# shield_1_axis.net
KiCad netlist of a schematic drawn in EAGLE
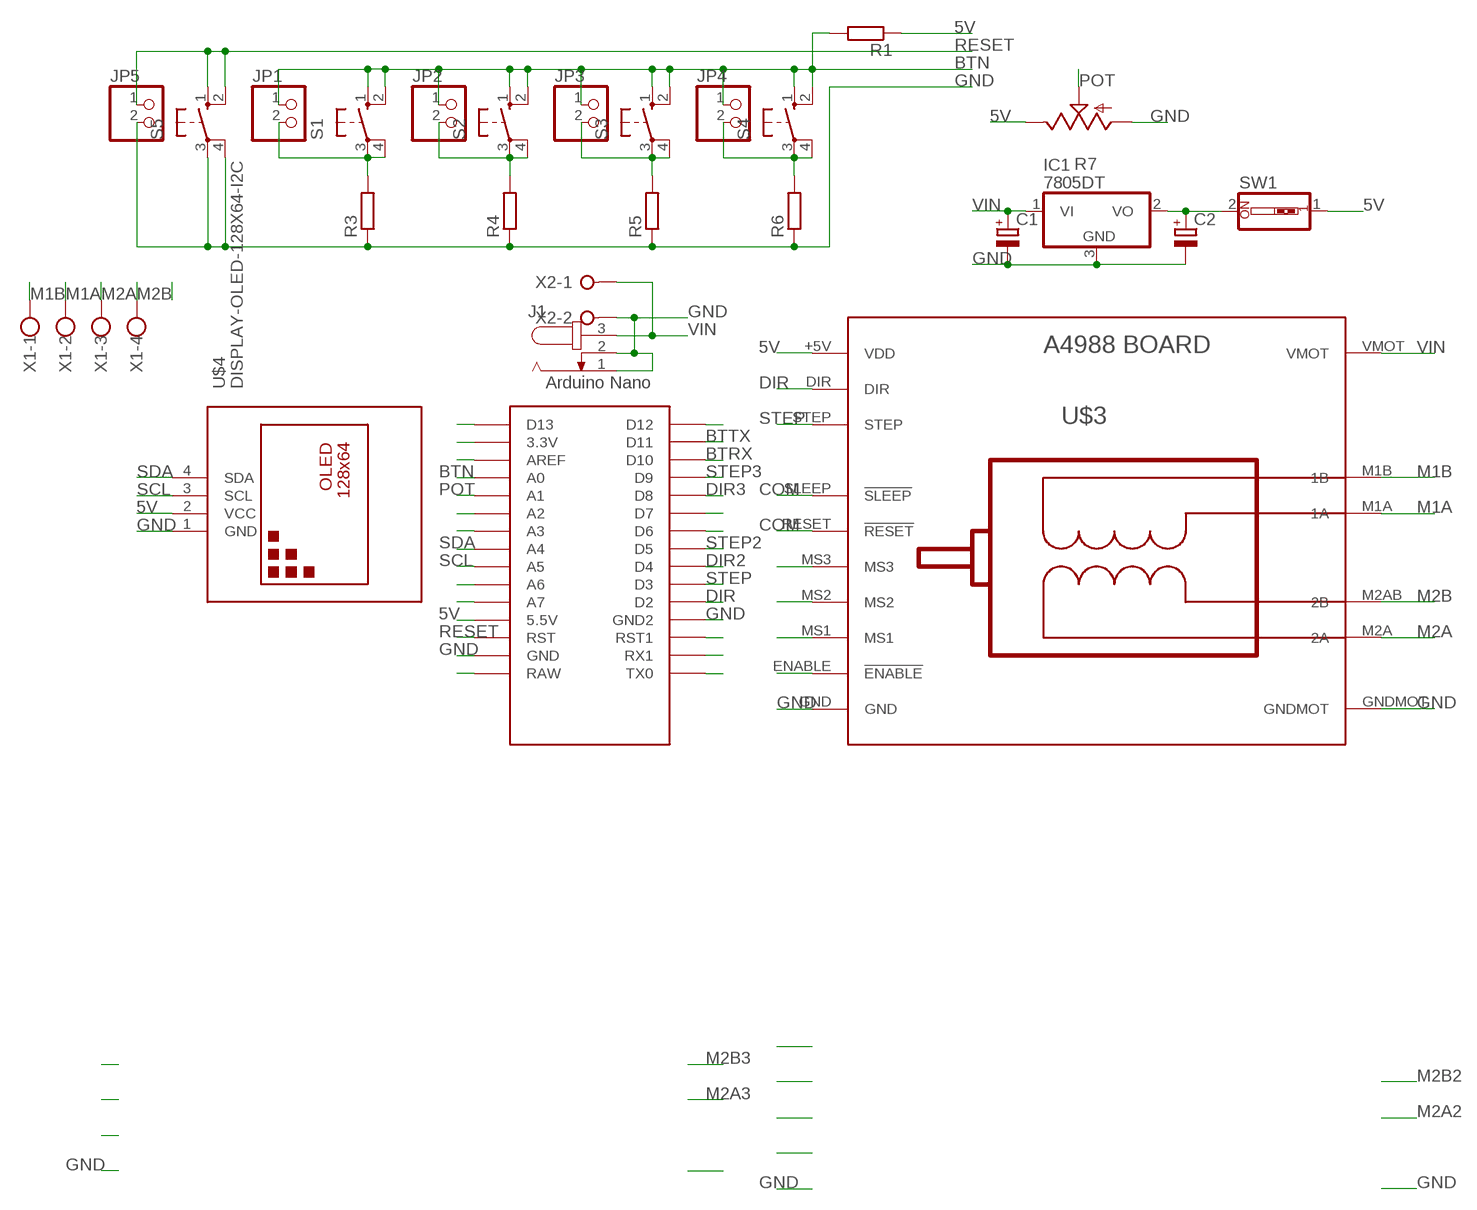
[diagram p0: schematic, sheet 1]

(export (version "E")
  (design (tool "Eeschema 10.0.6"))
  (components
    (comp (ref "C1")
      (value "CPOL-EUE2.5-7")
      (footprint "eagle-import:E2,5-7")
      (libsource (lib "eagle-import") (part "CPOL-EUE2.5-7"))
    )
    (comp (ref "C2")
      (value "CPOL-EUE2.5-7")
      (footprint "eagle-import:E2,5-7")
      (libsource (lib "eagle-import") (part "CPOL-EUE2.5-7"))
    )
    (comp (ref "IC1")
      (value "7805DT")
      (footprint "eagle-import:TO252")
      (libsource (lib "eagle-import") (part "78DT05"))
    )
    (comp (ref "J1")
      (value "JACK-PLUG1")
      (footprint "eagle-import:SPC4078")
      (libsource (lib "eagle-import") (part "JACK-PLUG1"))
    )
    (comp (ref "JP1")
      (value "PINHD-1X2")
      (footprint "eagle-import:1X02")
      (libsource (lib "eagle-import") (part "PINHD-1X2"))
    )
    (comp (ref "JP2")
      (value "PINHD-1X2")
      (footprint "eagle-import:1X02")
      (libsource (lib "eagle-import") (part "PINHD-1X2"))
    )
    (comp (ref "JP3")
      (value "PINHD-1X2")
      (footprint "eagle-import:1X02")
      (libsource (lib "eagle-import") (part "PINHD-1X2"))
    )
    (comp (ref "JP4")
      (value "PINHD-1X2")
      (footprint "eagle-import:1X02")
      (libsource (lib "eagle-import") (part "PINHD-1X2"))
    )
    (comp (ref "JP5")
      (value "PINHD-1X2")
      (footprint "eagle-import:1X02")
      (libsource (lib "eagle-import") (part "PINHD-1X2"))
    )
    (comp (ref "R1")
      (value "R-EU_R1206")
      (footprint "eagle-import:R1206")
      (libsource (lib "eagle-import") (part "R-EU_R1206"))
    )
    (comp (ref "R3")
      (value "R-EU_R1206")
      (footprint "eagle-import:R1206")
      (libsource (lib "eagle-import") (part "R-EU_R1206"))
    )
    (comp (ref "R4")
      (value "R-EU_R1206")
      (footprint "eagle-import:R1206")
      (libsource (lib "eagle-import") (part "R-EU_R1206"))
    )
    (comp (ref "R5")
      (value "R-EU_R1206")
      (footprint "eagle-import:R1206")
      (libsource (lib "eagle-import") (part "R-EU_R1206"))
    )
    (comp (ref "R6")
      (value "R-EU_R1206")
      (footprint "eagle-import:R1206")
      (libsource (lib "eagle-import") (part "R-EU_R1206"))
    )
    (comp (ref "R7")
      (value "TRIM_US-S63S")
      (footprint "eagle-import:S63S")
      (libsource (lib "eagle-import") (part "TRIM_US-S63S"))
    )
    (comp (ref "S1")
      (value "40-XX")
      (footprint "eagle-import:B3F-40XX")
      (fields (field (name "MF") "OMRON COMPONENTS USA") (field (name "MPN") "B3F-4000"))
      (libsource (lib "eagle-import") (part "40-XX"))
    )
    (comp (ref "S2")
      (value "40-XX")
      (footprint "eagle-import:B3F-40XX")
      (fields (field (name "MF") "OMRON COMPONENTS USA") (field (name "MPN") "B3F-4000"))
      (libsource (lib "eagle-import") (part "40-XX"))
    )
    (comp (ref "S3")
      (value "40-XX")
      (footprint "eagle-import:B3F-40XX")
      (fields (field (name "MF") "OMRON COMPONENTS USA") (field (name "MPN") "B3F-4000"))
      (libsource (lib "eagle-import") (part "40-XX"))
    )
    (comp (ref "S4")
      (value "40-XX")
      (footprint "eagle-import:B3F-40XX")
      (fields (field (name "MF") "OMRON COMPONENTS USA") (field (name "MPN") "B3F-4000"))
      (libsource (lib "eagle-import") (part "40-XX"))
    )
    (comp (ref "S5")
      (value "10-XX")
      (footprint "eagle-import:B3F-10XX")
      (fields (field (name "MPN") "B3F-1000"))
      (libsource (lib "eagle-import") (part "10-XX"))
    )
    (comp (ref "SW1")
      (value "SW_DIP-1")
      (footprint "eagle-import:EDG-01")
      (libsource (lib "eagle-import") (part "SW_DIP-1"))
    )
    (comp (ref "U$1")
      (value "NANO")
      (footprint "eagle-import:NANO")
      (libsource (lib "eagle-import") (part "NANO"))
    )
    (comp (ref "U$3")
      (value "BOARD_A4988")
      (footprint "eagle-import:BOARD_A4988")
      (libsource (lib "eagle-import") (part "BOARD_A4988"))
    )
    (comp (ref "U$4")
      (value "DISPLAY-OLED-128X64-I2C")
      (footprint "eagle-import:DISPLAY-OLED-128X64-I2C")
      (libsource (lib "eagle-import") (part "DISPLAY-OLED-128X64-I2C"))
    )
    (comp (ref "X1")
      (value "W237-4")
      (footprint "eagle-import:W237-4")
      (libsource (lib "eagle-import") (part "W237-4"))
    )
    (comp (ref "X2")
      (value "W237-02P")
      (footprint "eagle-import:W237-132")
      (libsource (lib "eagle-import") (part "W237-02P"))
    )
  )
  (nets
    (net (code "1") (name "/5V") (class "Default")
      (node (ref "R1") (pin "1") (pinfunction "1_1") (pintype "passive"))
      (node (ref "R7") (pin "E") (pinfunction "E_E") (pintype "passive"))
      (node (ref "SW1") (pin "1") (pinfunction "1_1") (pintype "passive"))
      (node (ref "U$1") (pin "5V") (pinfunction "5.5V_5V") (pintype "bidirectional"))
      (node (ref "U$3") (pin "+5V") (pinfunction "VDD_+5V") (pintype "power_in"))
      (node (ref "U$4") (pin "2") (pinfunction "VCC_2") (pintype "power_in"))
    )
    (net (code "2") (name "/BTN") (class "Default")
      (node (ref "JP1") (pin "1") (pinfunction "1_1") (pintype "passive"))
      (node (ref "JP2") (pin "1") (pinfunction "1_1") (pintype "passive"))
      (node (ref "JP3") (pin "1") (pinfunction "1_1") (pintype "passive"))
      (node (ref "JP4") (pin "1") (pinfunction "1_1") (pintype "passive"))
      (node (ref "R1") (pin "2") (pinfunction "2_2") (pintype "passive"))
      (node (ref "S1") (pin "1") (pinfunction "S_1") (pintype "passive"))
      (node (ref "S1") (pin "2") (pinfunction "S1_2") (pintype "passive"))
      (node (ref "S2") (pin "1") (pinfunction "S_1") (pintype "passive"))
      (node (ref "S2") (pin "2") (pinfunction "S1_2") (pintype "passive"))
      (node (ref "S3") (pin "1") (pinfunction "S_1") (pintype "passive"))
      (node (ref "S3") (pin "2") (pinfunction "S1_2") (pintype "passive"))
      (node (ref "S4") (pin "1") (pinfunction "S_1") (pintype "passive"))
      (node (ref "S4") (pin "2") (pinfunction "S1_2") (pintype "passive"))
      (node (ref "U$1") (pin "A0") (pinfunction "A0_A0") (pintype "bidirectional"))
    )
    (net (code "3") (name "/BTRX") (class "Default")
      (node (ref "U$1") (pin "D10") (pinfunction "D10_D10") (pintype "bidirectional"))
    )
    (net (code "4") (name "/BTTX") (class "Default")
      (node (ref "U$1") (pin "D11") (pinfunction "D11_D11") (pintype "bidirectional"))
    )
    (net (code "5") (name "/COM") (class "Default")
      (node (ref "U$3") (pin "RESET") (pinfunction "~{RESET}_RESET") (pintype "input"))
      (node (ref "U$3") (pin "SLEEP") (pinfunction "~{SLEEP}_SLEEP") (pintype "input"))
    )
    (net (code "6") (name "/DIR") (class "Default")
      (node (ref "U$1") (pin "D2") (pinfunction "D2_D2") (pintype "bidirectional"))
      (node (ref "U$3") (pin "DIR") (pinfunction "DIR_DIR") (pintype "input"))
    )
    (net (code "7") (name "/DIR2") (class "Default")
      (node (ref "U$1") (pin "D4") (pinfunction "D4_D4") (pintype "bidirectional"))
    )
    (net (code "8") (name "/DIR3") (class "Default")
      (node (ref "U$1") (pin "D8") (pinfunction "D8_D8") (pintype "bidirectional"))
    )
    (net (code "9") (name "/GND") (class "Default")
      (node (ref "C1") (pin "-") (pinfunction "-_-") (pintype "passive"))
      (node (ref "C2") (pin "-") (pinfunction "-_-") (pintype "passive"))
      (node (ref "IC1") (pin "3") (pinfunction "GND_3") (pintype "passive"))
      (node (ref "J1") (pin "1") (pinfunction "1_1") (pintype "passive"))
      (node (ref "J1") (pin "2") (pinfunction "2_2") (pintype "passive"))
      (node (ref "JP5") (pin "2") (pinfunction "2_2") (pintype "passive"))
      (node (ref "R3") (pin "1") (pinfunction "1_1") (pintype "passive"))
      (node (ref "R4") (pin "1") (pinfunction "1_1") (pintype "passive"))
      (node (ref "R5") (pin "1") (pinfunction "1_1") (pintype "passive"))
      (node (ref "R6") (pin "1") (pinfunction "1_1") (pintype "passive"))
      (node (ref "R7") (pin "A") (pinfunction "A_A") (pintype "passive"))
      (node (ref "S5") (pin "3") (pinfunction "P_3") (pintype "passive"))
      (node (ref "S5") (pin "4") (pinfunction "P1_4") (pintype "passive"))
      (node (ref "U$1") (pin "GND") (pinfunction "GND_GND") (pintype "bidirectional"))
      (node (ref "U$1") (pin "GND1") (pinfunction "GND2_GND1") (pintype "bidirectional"))
      (node (ref "U$3") (pin "GND") (pinfunction "GND_GND") (pintype "power_in"))
      (node (ref "U$3") (pin "GNDMOT") (pinfunction "GNDMOT_GNDMOT") (pintype "power_in"))
      (node (ref "U$4") (pin "1") (pinfunction "GND_1") (pintype "power_in"))
      (node (ref "X2") (pin "2") (pinfunction "KL_2") (pintype "passive"))
    )
    (net (code "10") (name "/M1A") (class "Default")
      (node (ref "U$3") (pin "M1A") (pinfunction "1A_M1A") (pintype "output"))
      (node (ref "X1") (pin "2") (pinfunction "KL_2") (pintype "passive"))
    )
    (net (code "11") (name "/M1B") (class "Default")
      (node (ref "U$3") (pin "M1B") (pinfunction "1B_M1B") (pintype "output"))
      (node (ref "X1") (pin "1") (pinfunction "KL_1") (pintype "passive"))
    )
    (net (code "12") (name "/M2A") (class "Default")
      (node (ref "U$3") (pin "M2A") (pinfunction "2A_M2A") (pintype "output"))
      (node (ref "X1") (pin "3") (pinfunction "KL_3") (pintype "passive"))
    )
    (net (code "15") (name "/M2B") (class "Default")
      (node (ref "U$3") (pin "M2AB") (pinfunction "2B_M2AB") (pintype "output"))
      (node (ref "X1") (pin "4") (pinfunction "KL_4") (pintype "passive"))
    )
    (net (code "18") (name "/POT") (class "Default")
      (node (ref "R7") (pin "S") (pinfunction "S_S") (pintype "passive"))
      (node (ref "U$1") (pin "A1") (pinfunction "A1_A1") (pintype "bidirectional"))
    )
    (net (code "19") (name "/RESET") (class "Default")
      (node (ref "JP5") (pin "1") (pinfunction "1_1") (pintype "passive"))
      (node (ref "S5") (pin "1") (pinfunction "S_1") (pintype "passive"))
      (node (ref "S5") (pin "2") (pinfunction "S1_2") (pintype "passive"))
      (node (ref "U$1") (pin "RST") (pinfunction "RST_RST") (pintype "bidirectional"))
    )
    (net (code "20") (name "/SCL") (class "Default")
      (node (ref "U$1") (pin "A5") (pinfunction "A5_A5") (pintype "bidirectional"))
      (node (ref "U$4") (pin "3") (pinfunction "SCL_3") (pintype "bidirectional"))
    )
    (net (code "21") (name "/SDA") (class "Default")
      (node (ref "U$1") (pin "A4") (pinfunction "A4_A4") (pintype "bidirectional"))
      (node (ref "U$4") (pin "4") (pinfunction "SDA_4") (pintype "bidirectional"))
    )
    (net (code "22") (name "/STEP") (class "Default")
      (node (ref "U$1") (pin "D3") (pinfunction "D3_D3") (pintype "bidirectional"))
      (node (ref "U$3") (pin "STEP") (pinfunction "STEP_STEP") (pintype "input"))
    )
    (net (code "23") (name "/STEP2") (class "Default")
      (node (ref "U$1") (pin "D5") (pinfunction "D5_D5") (pintype "bidirectional"))
    )
    (net (code "24") (name "/STEP3") (class "Default")
      (node (ref "U$1") (pin "D9") (pinfunction "D9_D9") (pintype "bidirectional"))
    )
    (net (code "25") (name "/VIN") (class "Default")
      (node (ref "C1") (pin "+") (pinfunction "+_+") (pintype "passive"))
      (node (ref "IC1") (pin "1") (pinfunction "VI_1") (pintype "input"))
      (node (ref "J1") (pin "3") (pinfunction "3_3") (pintype "passive"))
      (node (ref "U$3") (pin "VMOT") (pinfunction "VMOT_VMOT") (pintype "power_in"))
      (node (ref "X2") (pin "1") (pinfunction "KL_1") (pintype "passive"))
    )
    (net (code "26") (name "Net-(IC1-VO)") (class "Default")
      (node (ref "C2") (pin "+") (pinfunction "+_+") (pintype "passive"))
      (node (ref "IC1") (pin "2") (pinfunction "VO_2") (pintype "passive"))
      (node (ref "SW1") (pin "2") (pinfunction "2_2") (pintype "passive"))
    )
    (net (code "27") (name "Net-(S1-P)") (class "Default")
      (node (ref "JP1") (pin "2") (pinfunction "2_2") (pintype "passive"))
      (node (ref "R3") (pin "2") (pinfunction "2_2") (pintype "passive"))
      (node (ref "S1") (pin "3") (pinfunction "P_3") (pintype "passive"))
      (node (ref "S1") (pin "4") (pinfunction "P1_4") (pintype "passive"))
    )
    (net (code "28") (name "Net-(S2-P)") (class "Default")
      (node (ref "JP2") (pin "2") (pinfunction "2_2") (pintype "passive"))
      (node (ref "R4") (pin "2") (pinfunction "2_2") (pintype "passive"))
      (node (ref "S2") (pin "3") (pinfunction "P_3") (pintype "passive"))
      (node (ref "S2") (pin "4") (pinfunction "P1_4") (pintype "passive"))
    )
    (net (code "29") (name "Net-(S3-P)") (class "Default")
      (node (ref "JP3") (pin "2") (pinfunction "2_2") (pintype "passive"))
      (node (ref "R5") (pin "2") (pinfunction "2_2") (pintype "passive"))
      (node (ref "S3") (pin "3") (pinfunction "P_3") (pintype "passive"))
      (node (ref "S3") (pin "4") (pinfunction "P1_4") (pintype "passive"))
    )
    (net (code "30") (name "Net-(S4-P)") (class "Default")
      (node (ref "JP4") (pin "2") (pinfunction "2_2") (pintype "passive"))
      (node (ref "R6") (pin "2") (pinfunction "2_2") (pintype "passive"))
      (node (ref "S4") (pin "3") (pinfunction "P_3") (pintype "passive"))
      (node (ref "S4") (pin "4") (pinfunction "P1_4") (pintype "passive"))
    )
    (net (code "31") (name "unconnected-(U$1-Pad3.3V)") (class "Default")
      (node (ref "U$1") (pin "3.3V") (pinfunction "3.3V_3.3V") (pintype "bidirectional"))
    )
    (net (code "32") (name "unconnected-(U$1-PadA2)") (class "Default")
      (node (ref "U$1") (pin "A2") (pinfunction "A2_A2") (pintype "bidirectional"))
    )
    (net (code "33") (name "unconnected-(U$1-PadA3)") (class "Default")
      (node (ref "U$1") (pin "A3") (pinfunction "A3_A3") (pintype "bidirectional"))
    )
    (net (code "34") (name "unconnected-(U$1-PadA6)") (class "Default")
      (node (ref "U$1") (pin "A6") (pinfunction "A6_A6") (pintype "bidirectional"))
    )
    (net (code "35") (name "unconnected-(U$1-PadA7)") (class "Default")
      (node (ref "U$1") (pin "A7") (pinfunction "A7_A7") (pintype "bidirectional"))
    )
    (net (code "36") (name "unconnected-(U$1-PadAREF)") (class "Default")
      (node (ref "U$1") (pin "AREF") (pinfunction "AREF_AREF") (pintype "bidirectional"))
    )
    (net (code "37") (name "unconnected-(U$1-PadD6)") (class "Default")
      (node (ref "U$1") (pin "D6") (pinfunction "D6_D6") (pintype "bidirectional"))
    )
    (net (code "38") (name "unconnected-(U$1-PadD7)") (class "Default")
      (node (ref "U$1") (pin "D7") (pinfunction "D7_D7") (pintype "bidirectional"))
    )
    (net (code "39") (name "unconnected-(U$1-PadD12)") (class "Default")
      (node (ref "U$1") (pin "D12") (pinfunction "D12_D12") (pintype "bidirectional"))
    )
    (net (code "40") (name "unconnected-(U$1-PadD13)") (class "Default")
      (node (ref "U$1") (pin "D13") (pinfunction "D13_D13") (pintype "bidirectional"))
    )
    (net (code "41") (name "unconnected-(U$1-PadICSP1)") (class "Default")
      (node (ref "U$1") (pin "ICSP1") (pinfunction "ICSP1_ICSP1") (pintype "bidirectional"))
    )
    (net (code "42") (name "unconnected-(U$1-PadICSP2)") (class "Default")
      (node (ref "U$1") (pin "ICSP2") (pinfunction "ICSP2_ICSP2") (pintype "bidirectional"))
    )
    (net (code "43") (name "unconnected-(U$1-PadICSP3)") (class "Default")
      (node (ref "U$1") (pin "ICSP3") (pinfunction "ICSP3_ICSP3") (pintype "bidirectional"))
    )
    (net (code "44") (name "unconnected-(U$1-PadICSP4)") (class "Default")
      (node (ref "U$1") (pin "ICSP4") (pinfunction "ICSP4_ICSP4") (pintype "bidirectional"))
    )
    (net (code "45") (name "unconnected-(U$1-PadICSP5)") (class "Default")
      (node (ref "U$1") (pin "ICSP5") (pinfunction "ICSP5_ICSP5") (pintype "bidirectional"))
    )
    (net (code "46") (name "unconnected-(U$1-PadICSP6)") (class "Default")
      (node (ref "U$1") (pin "ICSP6") (pinfunction "ICSP6_ICSP6") (pintype "bidirectional"))
    )
    (net (code "47") (name "unconnected-(U$1-PadRAW)") (class "Default")
      (node (ref "U$1") (pin "RAW") (pinfunction "RAW_RAW") (pintype "bidirectional"))
    )
    (net (code "48") (name "unconnected-(U$1-PadRST1)") (class "Default")
      (node (ref "U$1") (pin "RST1") (pinfunction "RST1_RST1") (pintype "bidirectional"))
    )
    (net (code "49") (name "unconnected-(U$1-PadRX1)") (class "Default")
      (node (ref "U$1") (pin "RX1") (pinfunction "RX1_RX1") (pintype "bidirectional"))
    )
    (net (code "50") (name "unconnected-(U$1-PadTX0)") (class "Default")
      (node (ref "U$1") (pin "TX0") (pinfunction "TX0_TX0") (pintype "bidirectional"))
    )
    (net (code "51") (name "unconnected-(U$3-PadMS1)") (class "Default")
      (node (ref "U$3") (pin "MS1") (pinfunction "MS1_MS1") (pintype "input"))
    )
    (net (code "52") (name "unconnected-(U$3-PadMS2)") (class "Default")
      (node (ref "U$3") (pin "MS2") (pinfunction "MS2_MS2") (pintype "input"))
    )
    (net (code "53") (name "unconnected-(U$3-PadMS3)") (class "Default")
      (node (ref "U$3") (pin "MS3") (pinfunction "MS3_MS3") (pintype "input"))
    )
    (net (code "54") (name "unconnected-(U$3-~{ENABLE}-PadENABLE)") (class "Default")
      (node (ref "U$3") (pin "ENABLE") (pinfunction "~{ENABLE}_ENABLE") (pintype "input"))
    )
  )
)
